# control_v2.net
KiCad netlist of a schematic drawn in EAGLE
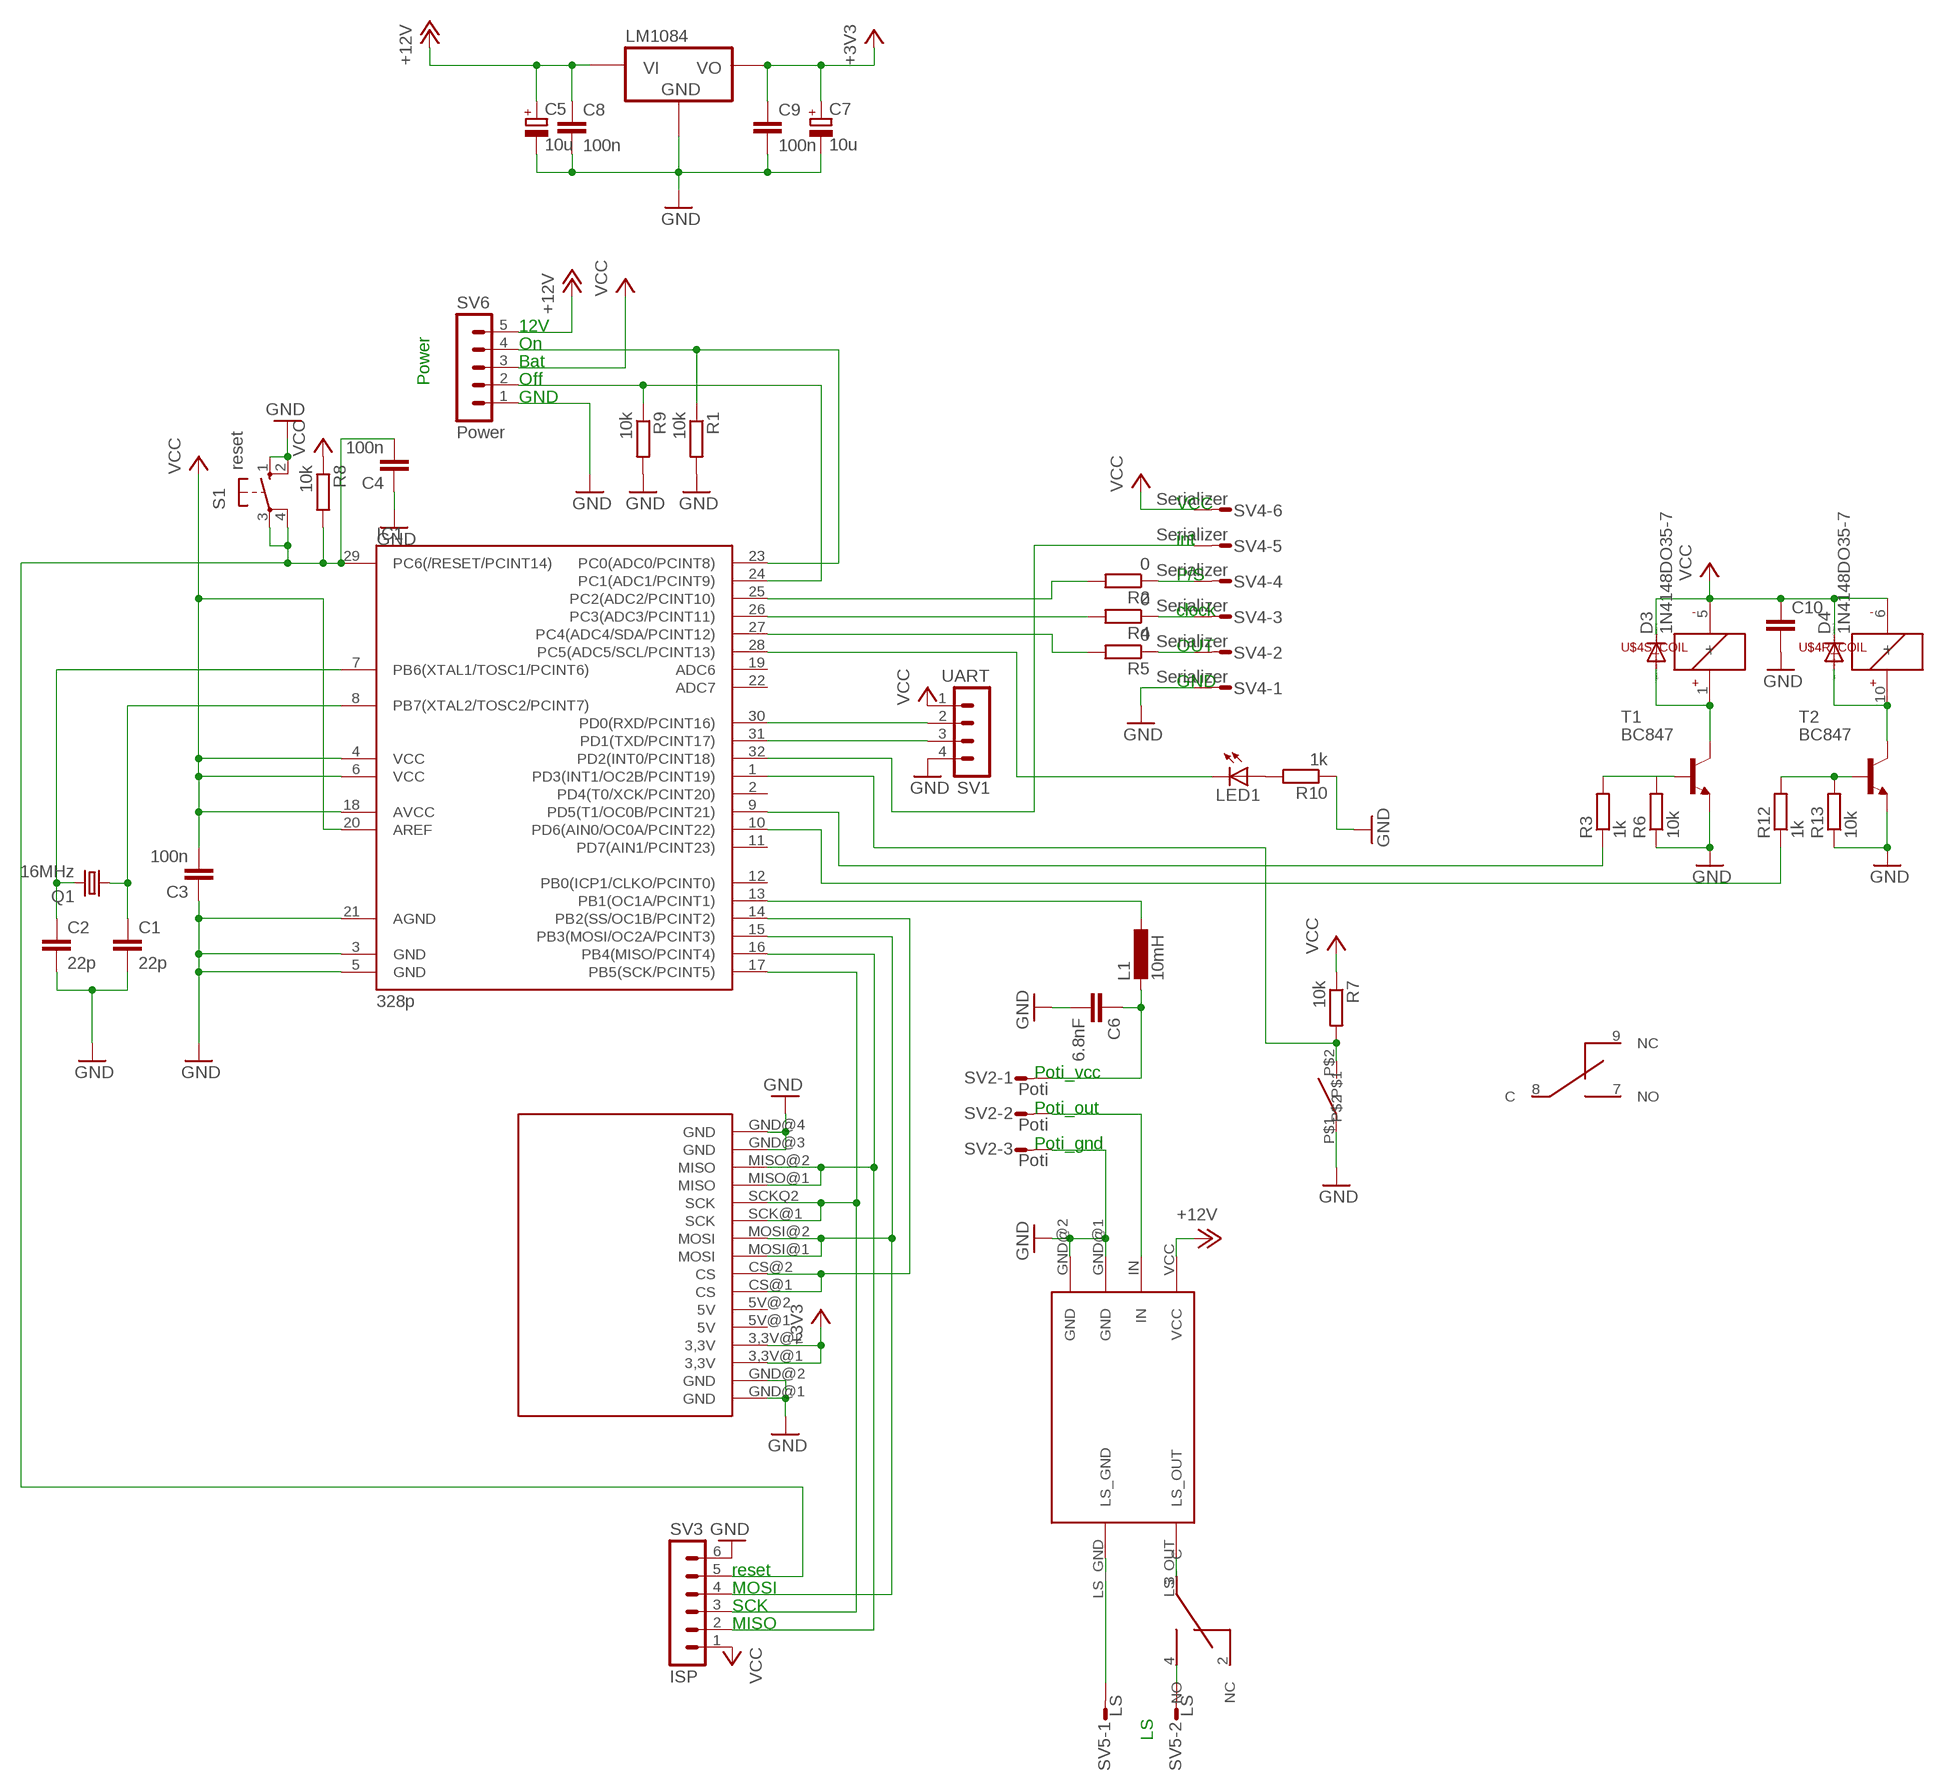
[diagram p0: schematic, sheet 1]

(export (version "E")
  (design (tool "Eeschema 10.0.6"))
  (components
    (comp (ref "C1")
      (value "22p")
      (footprint "eagle-import:C1206")
      (libsource (lib "eagle-import") (part "C-EUC1206"))
    )
    (comp (ref "C2")
      (value "22p")
      (footprint "eagle-import:C1206")
      (libsource (lib "eagle-import") (part "C-EUC1206"))
    )
    (comp (ref "C3")
      (value "100n")
      (footprint "eagle-import:C1206")
      (libsource (lib "eagle-import") (part "C-EUC1206"))
    )
    (comp (ref "C4")
      (value "100n")
      (footprint "eagle-import:C1206")
      (libsource (lib "eagle-import") (part "C-EUC1206"))
    )
    (comp (ref "C5")
      (value "10u")
      (footprint "eagle-import:E2,5-7")
      (libsource (lib "eagle-import") (part "CPOL-EUE2.5-7"))
    )
    (comp (ref "C6")
      (value "6.8nF")
      (footprint "eagle-import:C050-024X044")
      (libsource (lib "eagle-import") (part "C-EU050-024X044"))
    )
    (comp (ref "C7")
      (value "10u")
      (footprint "eagle-import:E2,5-7")
      (libsource (lib "eagle-import") (part "CPOL-EUE2.5-7"))
    )
    (comp (ref "C8")
      (value "100n")
      (footprint "eagle-import:C1206")
      (libsource (lib "eagle-import") (part "C-EUC1206"))
    )
    (comp (ref "C9")
      (value "100n")
      (footprint "eagle-import:C1206")
      (libsource (lib "eagle-import") (part "C-EUC1206"))
    )
    (comp (ref "C10")
      (value "C-EUC1206")
      (footprint "eagle-import:C1206")
      (libsource (lib "eagle-import") (part "C-EUC1206"))
    )
    (comp (ref "D3")
      (value "1N4148DO35-7")
      (footprint "eagle-import:DO35-7")
      (libsource (lib "eagle-import") (part "1N4148DO35-7"))
    )
    (comp (ref "D4")
      (value "1N4148DO35-7")
      (footprint "eagle-import:DO35-7")
      (libsource (lib "eagle-import") (part "1N4148DO35-7"))
    )
    (comp (ref "IC1")
      (value "328p")
      (footprint "eagle-import:TQFP32-08")
      (libsource (lib "eagle-import") (part "MEGA48/88/168-AU"))
    )
    (comp (ref "L1")
      (value "10mH")
      (footprint "eagle-import:0207_5V")
      (libsource (lib "eagle-import") (part "L-EU0207/5V"))
    )
    (comp (ref "LED1")
      (value "LEDCHIPLED_1206")
      (footprint "eagle-import:CHIPLED_1206")
      (libsource (lib "eagle-import") (part "LEDCHIPLED_1206"))
    )
    (comp (ref "Q1")
      (value "16MHz")
      (footprint "eagle-import:HC49UP")
      (libsource (lib "eagle-import") (part "CRYSTALHC49UP"))
    )
    (comp (ref "R1")
      (value "10k")
      (footprint "eagle-import:M1206")
      (libsource (lib "eagle-import") (part "R-EU_M1206"))
    )
    (comp (ref "R2")
      (value "0")
      (footprint "eagle-import:M1206")
      (libsource (lib "eagle-import") (part "R-EU_M1206"))
    )
    (comp (ref "R3")
      (value "1k")
      (footprint "eagle-import:M1206")
      (libsource (lib "eagle-import") (part "R-EU_M1206"))
    )
    (comp (ref "R4")
      (value "0")
      (footprint "eagle-import:M1206")
      (libsource (lib "eagle-import") (part "R-EU_M1206"))
    )
    (comp (ref "R5")
      (value "0")
      (footprint "eagle-import:M1206")
      (libsource (lib "eagle-import") (part "R-EU_M1206"))
    )
    (comp (ref "R6")
      (value "10k")
      (footprint "eagle-import:M1206")
      (libsource (lib "eagle-import") (part "R-EU_M1206"))
    )
    (comp (ref "R7")
      (value "10k")
      (footprint "eagle-import:M1206")
      (libsource (lib "eagle-import") (part "R-EU_M1206"))
    )
    (comp (ref "R8")
      (value "10k")
      (footprint "eagle-import:M1206")
      (libsource (lib "eagle-import") (part "R-EU_M1206"))
    )
    (comp (ref "R9")
      (value "10k")
      (footprint "eagle-import:M1206")
      (libsource (lib "eagle-import") (part "R-EU_M1206"))
    )
    (comp (ref "R10")
      (value "1k")
      (footprint "eagle-import:M1206")
      (libsource (lib "eagle-import") (part "R-EU_M1206"))
    )
    (comp (ref "R12")
      (value "1k")
      (footprint "eagle-import:M1206")
      (libsource (lib "eagle-import") (part "R-EU_M1206"))
    )
    (comp (ref "R13")
      (value "10k")
      (footprint "eagle-import:M1206")
      (libsource (lib "eagle-import") (part "R-EU_M1206"))
    )
    (comp (ref "S1")
      (value "reset")
      (footprint "eagle-import:B3F-10XX")
      (fields (field (name "MPN") "B3F-1000"))
      (libsource (lib "eagle-import") (part "10-XX"))
    )
    (comp (ref "SV1")
      (value "UART")
      (footprint "eagle-import:MA04-1")
      (libsource (lib "eagle-import") (part "MA04-1"))
    )
    (comp (ref "SV2")
      (value "Poti")
      (footprint "eagle-import:S03P")
      (libsource (lib "eagle-import") (part "S03P"))
    )
    (comp (ref "SV3")
      (value "ISP")
      (footprint "eagle-import:MA06-1")
      (libsource (lib "eagle-import") (part "MA06-1"))
    )
    (comp (ref "SV4")
      (value "Serializer")
      (footprint "eagle-import:S06P")
      (libsource (lib "eagle-import") (part "S06P"))
    )
    (comp (ref "SV5")
      (value "LS")
      (footprint "eagle-import:S02P")
      (libsource (lib "eagle-import") (part "S02P"))
    )
    (comp (ref "SV6")
      (value "Power")
      (footprint "eagle-import:MA05-1")
      (libsource (lib "eagle-import") (part "MA05-1"))
    )
    (comp (ref "T1")
      (value "BC847")
      (footprint "eagle-import:SOT23-BEC")
      (libsource (lib "eagle-import") (part "-NPN-SOT23-BECBC847"))
    )
    (comp (ref "T2")
      (value "BC847")
      (footprint "eagle-import:SOT23-BEC")
      (libsource (lib "eagle-import") (part "-NPN-SOT23-BECBC847"))
    )
    (comp (ref "U$1")
      (value "TILT")
      (footprint "eagle-import:TILT")
      (libsource (lib "eagle-import") (part "TILT"))
    )
    (comp (ref "U$2")
      (value "AMP")
      (footprint "eagle-import:AMP")
      (libsource (lib "eagle-import") (part "AMP"))
    )
    (comp (ref "U$3")
      (value "SD_CARD_HOLDER")
      (footprint "eagle-import:SD_CARD_HOLDER")
      (libsource (lib "eagle-import") (part "SD_CARD_HOLDER"))
    )
    (comp (ref "U$4")
      (value "EB2-4.5TNU")
      (footprint "eagle-import:10PIN_SMD_RELAY")
      (libsource (lib "eagle-import") (part "EB2-4.5TNU"))
    )
    (comp (ref "U$5")
      (value "LD1117")
      (footprint "eagle-import:TO220V")
      (libsource (lib "eagle-import") (part "LD1117"))
    )
  )
  (nets
    (net (code "1") (name "+3V3") (class "Default")
      (node (ref "C7") (pin "+") (pinfunction "+_+") (pintype "passive"))
      (node (ref "C9") (pin "1") (pinfunction "1_1") (pintype "passive"))
      (node (ref "U$3") (pin "3,3V@1") (pinfunction "3,3V_3,3V@1") (pintype "bidirectional"))
      (node (ref "U$3") (pin "3,3V@2") (pinfunction "3,3V_3,3V@2") (pintype "bidirectional"))
      (node (ref "U$5") (pin "2") (pinfunction "VO_2") (pintype "bidirectional"))
    )
    (net (code "2") (name "+12V") (class "Default")
      (node (ref "C5") (pin "+") (pinfunction "+_+") (pintype "passive"))
      (node (ref "C8") (pin "1") (pinfunction "1_1") (pintype "passive"))
      (node (ref "SV6") (pin "5") (pinfunction "5_5") (pintype "passive"))
      (node (ref "U$2") (pin "VCC") (pinfunction "VCC_VCC") (pintype "bidirectional"))
      (node (ref "U$5") (pin "3") (pinfunction "VI_3") (pintype "input"))
    )
    (net (code "3") (name "GND") (class "Default")
      (node (ref "C1") (pin "2") (pinfunction "2_2") (pintype "passive"))
      (node (ref "C10") (pin "2") (pinfunction "2_2") (pintype "passive"))
      (node (ref "C2") (pin "2") (pinfunction "2_2") (pintype "passive"))
      (node (ref "C3") (pin "1") (pinfunction "1_1") (pintype "passive"))
      (node (ref "C4") (pin "1") (pinfunction "1_1") (pintype "passive"))
      (node (ref "C5") (pin "-") (pinfunction "-_-") (pintype "passive"))
      (node (ref "C6") (pin "2") (pinfunction "2_2") (pintype "passive"))
      (node (ref "C7") (pin "-") (pinfunction "-_-") (pintype "passive"))
      (node (ref "C8") (pin "2") (pinfunction "2_2") (pintype "passive"))
      (node (ref "C9") (pin "2") (pinfunction "2_2") (pintype "passive"))
      (node (ref "IC1") (pin "21") (pinfunction "AGND_21") (pintype "power_in"))
      (node (ref "IC1") (pin "3") (pinfunction "GND_3") (pintype "power_in"))
      (node (ref "IC1") (pin "5") (pinfunction "GND_5") (pintype "power_in"))
      (node (ref "R1") (pin "2") (pinfunction "2_2") (pintype "passive"))
      (node (ref "R10") (pin "1") (pinfunction "1_1") (pintype "passive"))
      (node (ref "R13") (pin "1") (pinfunction "1_1") (pintype "passive"))
      (node (ref "R6") (pin "1") (pinfunction "1_1") (pintype "passive"))
      (node (ref "R9") (pin "2") (pinfunction "2_2") (pintype "passive"))
      (node (ref "S1") (pin "1") (pinfunction "S_1") (pintype "passive"))
      (node (ref "S1") (pin "2") (pinfunction "S1_2") (pintype "passive"))
      (node (ref "SV1") (pin "4") (pinfunction "4_4") (pintype "passive"))
      (node (ref "SV2") (pin "3") (pinfunction "S_3") (pintype "passive"))
      (node (ref "SV3") (pin "6") (pinfunction "6_6") (pintype "passive"))
      (node (ref "SV4") (pin "1") (pinfunction "S_1") (pintype "passive"))
      (node (ref "SV6") (pin "1") (pinfunction "1_1") (pintype "passive"))
      (node (ref "T1") (pin "E") (pinfunction "E_E") (pintype "passive"))
      (node (ref "T2") (pin "E") (pinfunction "E_E") (pintype "passive"))
      (node (ref "U$1") (pin "P$1") (pinfunction "P$1_P$1") (pintype "bidirectional"))
      (node (ref "U$2") (pin "GND@1") (pinfunction "GND_GND@1") (pintype "bidirectional"))
      (node (ref "U$2") (pin "GND@2") (pinfunction "GND_GND@2") (pintype "bidirectional"))
      (node (ref "U$3") (pin "GND@1") (pinfunction "GND_GND@1") (pintype "bidirectional"))
      (node (ref "U$3") (pin "GND@2") (pinfunction "GND_GND@2") (pintype "bidirectional"))
      (node (ref "U$3") (pin "GND@3") (pinfunction "GND_GND@3") (pintype "bidirectional"))
      (node (ref "U$3") (pin "GND@4") (pinfunction "GND_GND@4") (pintype "bidirectional"))
      (node (ref "U$5") (pin "1") (pinfunction "GND_1") (pintype "bidirectional"))
    )
    (net (code "4") (name "Net-(IC1-PB1(OC1A{slash}PCINT1))") (class "Default")
      (node (ref "IC1") (pin "13") (pinfunction "PB1(OC1A/PCINT1)_13") (pintype "bidirectional"))
      (node (ref "L1") (pin "1") (pinfunction "1_1") (pintype "passive"))
    )
    (net (code "5") (name "Net-(IC1-PB2(SS{slash}OC1B{slash}PCINT2))") (class "Default")
      (node (ref "IC1") (pin "14") (pinfunction "PB2(SS/OC1B/PCINT2)_14") (pintype "bidirectional"))
      (node (ref "U$3") (pin "CS@1") (pinfunction "CS_CS@1") (pintype "bidirectional"))
      (node (ref "U$3") (pin "CS@2") (pinfunction "CS_CS@2") (pintype "bidirectional"))
    )
    (net (code "6") (name "Net-(IC1-PB3(MOSI{slash}OC2A{slash}PCINT3))") (class "Default")
      (node (ref "IC1") (pin "15") (pinfunction "PB3(MOSI/OC2A/PCINT3)_15") (pintype "bidirectional"))
      (node (ref "SV3") (pin "4") (pinfunction "4_4") (pintype "passive"))
      (node (ref "U$3") (pin "MOSI@1") (pinfunction "MOSI_MOSI@1") (pintype "bidirectional"))
      (node (ref "U$3") (pin "MOSI@2") (pinfunction "MOSI_MOSI@2") (pintype "bidirectional"))
    )
    (net (code "7") (name "Net-(IC1-PB4(MISO{slash}PCINT4))") (class "Default")
      (node (ref "IC1") (pin "16") (pinfunction "PB4(MISO/PCINT4)_16") (pintype "bidirectional"))
      (node (ref "SV3") (pin "2") (pinfunction "2_2") (pintype "passive"))
      (node (ref "U$3") (pin "MISO@1") (pinfunction "MISO_MISO@1") (pintype "bidirectional"))
      (node (ref "U$3") (pin "MISO@2") (pinfunction "MISO_MISO@2") (pintype "bidirectional"))
    )
    (net (code "8") (name "Net-(IC1-PB5(SCK{slash}PCINT5))") (class "Default")
      (node (ref "IC1") (pin "17") (pinfunction "PB5(SCK/PCINT5)_17") (pintype "bidirectional"))
      (node (ref "SV3") (pin "3") (pinfunction "3_3") (pintype "passive"))
      (node (ref "U$3") (pin "SCK@1") (pinfunction "SCK_SCK@1") (pintype "bidirectional"))
      (node (ref "U$3") (pin "SCKQ2") (pinfunction "SCK_SCKQ2") (pintype "bidirectional"))
    )
    (net (code "9") (name "Net-(IC1-PB6(XTAL1{slash}TOSC1{slash}PCINT6))") (class "Default")
      (node (ref "C2") (pin "1") (pinfunction "1_1") (pintype "passive"))
      (node (ref "IC1") (pin "7") (pinfunction "PB6(XTAL1/TOSC1/PCINT6)_7") (pintype "bidirectional"))
      (node (ref "Q1") (pin "2") (pinfunction "2_2") (pintype "passive"))
    )
    (net (code "10") (name "Net-(IC1-PB7(XTAL2{slash}TOSC2{slash}PCINT7))") (class "Default")
      (node (ref "C1") (pin "1") (pinfunction "1_1") (pintype "passive"))
      (node (ref "IC1") (pin "8") (pinfunction "PB7(XTAL2/TOSC2/PCINT7)_8") (pintype "bidirectional"))
      (node (ref "Q1") (pin "1") (pinfunction "1_1") (pintype "passive"))
    )
    (net (code "11") (name "Net-(IC1-PC0(ADC0{slash}PCINT8))") (class "Default")
      (node (ref "IC1") (pin "23") (pinfunction "PC0(ADC0/PCINT8)_23") (pintype "bidirectional"))
      (node (ref "R1") (pin "1") (pinfunction "1_1") (pintype "passive"))
      (node (ref "SV6") (pin "4") (pinfunction "4_4") (pintype "passive"))
    )
    (net (code "12") (name "Net-(IC1-PC1(ADC1{slash}PCINT9))") (class "Default")
      (node (ref "IC1") (pin "24") (pinfunction "PC1(ADC1/PCINT9)_24") (pintype "bidirectional"))
      (node (ref "R9") (pin "1") (pinfunction "1_1") (pintype "passive"))
      (node (ref "SV6") (pin "2") (pinfunction "2_2") (pintype "passive"))
    )
    (net (code "13") (name "Net-(IC1-PC2(ADC2{slash}PCINT10))") (class "Default")
      (node (ref "IC1") (pin "25") (pinfunction "PC2(ADC2/PCINT10)_25") (pintype "bidirectional"))
      (node (ref "R2") (pin "2") (pinfunction "2_2") (pintype "passive"))
    )
    (net (code "14") (name "Net-(IC1-PC3(ADC3{slash}PCINT11))") (class "Default")
      (node (ref "IC1") (pin "26") (pinfunction "PC3(ADC3/PCINT11)_26") (pintype "bidirectional"))
      (node (ref "R4") (pin "2") (pinfunction "2_2") (pintype "passive"))
    )
    (net (code "15") (name "Net-(IC1-PC4(ADC4{slash}SDA{slash}PCINT12))") (class "Default")
      (node (ref "IC1") (pin "27") (pinfunction "PC4(ADC4/SDA/PCINT12)_27") (pintype "bidirectional"))
      (node (ref "R5") (pin "2") (pinfunction "2_2") (pintype "passive"))
    )
    (net (code "16") (name "Net-(IC1-PC5(ADC5{slash}SCL{slash}PCINT13))") (class "Default")
      (node (ref "IC1") (pin "28") (pinfunction "PC5(ADC5/SCL/PCINT13)_28") (pintype "bidirectional"))
      (node (ref "LED1") (pin "C") (pinfunction "C_C") (pintype "passive"))
    )
    (net (code "17") (name "Net-(IC1-PC6({slash}RESET{slash}PCINT14))") (class "Default")
      (node (ref "C4") (pin "2") (pinfunction "2_2") (pintype "passive"))
      (node (ref "IC1") (pin "29") (pinfunction "PC6(/RESET/PCINT14)_29") (pintype "bidirectional"))
      (node (ref "R8") (pin "2") (pinfunction "2_2") (pintype "passive"))
      (node (ref "S1") (pin "3") (pinfunction "P_3") (pintype "passive"))
      (node (ref "S1") (pin "4") (pinfunction "P1_4") (pintype "passive"))
      (node (ref "SV3") (pin "5") (pinfunction "5_5") (pintype "passive"))
    )
    (net (code "18") (name "Net-(IC1-PD0(RXD{slash}PCINT16))") (class "Default")
      (node (ref "IC1") (pin "30") (pinfunction "PD0(RXD/PCINT16)_30") (pintype "bidirectional"))
      (node (ref "SV1") (pin "2") (pinfunction "2_2") (pintype "passive"))
    )
    (net (code "19") (name "Net-(IC1-PD1(TXD{slash}PCINT17))") (class "Default")
      (node (ref "IC1") (pin "31") (pinfunction "PD1(TXD/PCINT17)_31") (pintype "bidirectional"))
      (node (ref "SV1") (pin "3") (pinfunction "3_3") (pintype "passive"))
    )
    (net (code "20") (name "Net-(IC1-PD2(INT0{slash}PCINT18))") (class "Default")
      (node (ref "IC1") (pin "32") (pinfunction "PD2(INT0/PCINT18)_32") (pintype "bidirectional"))
      (node (ref "SV4") (pin "5") (pinfunction "S_5") (pintype "passive"))
    )
    (net (code "21") (name "Net-(IC1-PD3(INT1{slash}OC2B{slash}PCINT19))") (class "Default")
      (node (ref "IC1") (pin "1") (pinfunction "PD3(INT1/OC2B/PCINT19)_1") (pintype "bidirectional"))
      (node (ref "R7") (pin "2") (pinfunction "2_2") (pintype "passive"))
      (node (ref "U$1") (pin "P$2") (pinfunction "P$2_P$2") (pintype "bidirectional"))
    )
    (net (code "22") (name "Net-(IC1-PD5(T1{slash}OC0B{slash}PCINT21))") (class "Default")
      (node (ref "IC1") (pin "9") (pinfunction "PD5(T1/OC0B/PCINT21)_9") (pintype "bidirectional"))
      (node (ref "R3") (pin "1") (pinfunction "1_1") (pintype "passive"))
    )
    (net (code "23") (name "Net-(IC1-PD6(AIN0{slash}OC0A{slash}PCINT22))") (class "Default")
      (node (ref "IC1") (pin "10") (pinfunction "PD6(AIN0/OC0A/PCINT22)_10") (pintype "bidirectional"))
      (node (ref "R12") (pin "1") (pinfunction "1_1") (pintype "passive"))
    )
    (net (code "24") (name "Net-(LED1-PadA)") (class "Default")
      (node (ref "LED1") (pin "A") (pinfunction "A_A") (pintype "passive"))
      (node (ref "R10") (pin "2") (pinfunction "2_2") (pintype "passive"))
    )
    (net (code "25") (name "Net-(R3-Pad2)") (class "Default")
      (node (ref "R3") (pin "2") (pinfunction "2_2") (pintype "passive"))
      (node (ref "R6") (pin "2") (pinfunction "2_2") (pintype "passive"))
      (node (ref "T1") (pin "B") (pinfunction "B_B") (pintype "passive"))
    )
    (net (code "26") (name "Net-(R12-Pad2)") (class "Default")
      (node (ref "R12") (pin "2") (pinfunction "2_2") (pintype "passive"))
      (node (ref "R13") (pin "2") (pinfunction "2_2") (pintype "passive"))
      (node (ref "T2") (pin "B") (pinfunction "B_B") (pintype "passive"))
    )
    (net (code "27") (name "Net-(SV2A-S)") (class "Default")
      (node (ref "C6") (pin "1") (pinfunction "1_1") (pintype "passive"))
      (node (ref "L1") (pin "2") (pinfunction "2_2") (pintype "passive"))
      (node (ref "SV2") (pin "1") (pinfunction "S_1") (pintype "passive"))
    )
    (net (code "28") (name "Net-(SV2B-S)") (class "Default")
      (node (ref "SV2") (pin "2") (pinfunction "S_2") (pintype "passive"))
      (node (ref "U$2") (pin "IN") (pinfunction "IN_IN") (pintype "bidirectional"))
    )
    (net (code "29") (name "Net-(SV4B-S)") (class "Default")
      (node (ref "R5") (pin "1") (pinfunction "1_1") (pintype "passive"))
      (node (ref "SV4") (pin "2") (pinfunction "S_2") (pintype "passive"))
    )
    (net (code "30") (name "Net-(SV4C-S)") (class "Default")
      (node (ref "R4") (pin "1") (pinfunction "1_1") (pintype "passive"))
      (node (ref "SV4") (pin "3") (pinfunction "S_3") (pintype "passive"))
    )
    (net (code "31") (name "Net-(SV4D-S)") (class "Default")
      (node (ref "R2") (pin "1") (pinfunction "1_1") (pintype "passive"))
      (node (ref "SV4") (pin "4") (pinfunction "S_4") (pintype "passive"))
    )
    (net (code "32") (name "Net-(SV5A-S)") (class "Default")
      (node (ref "SV5") (pin "1") (pinfunction "S_1") (pintype "passive"))
      (node (ref "U$2") (pin "LS_GND") (pinfunction "LS_GND_LS_GND") (pintype "bidirectional"))
    )
    (net (code "33") (name "Net-(SV5B-S)") (class "Default")
      (node (ref "SV5") (pin "2") (pinfunction "S_2") (pintype "passive"))
      (node (ref "U$4") (pin "4") (pinfunction "NO_4") (pintype "bidirectional"))
    )
    (net (code "34") (name "Net-(U$4A-+)") (class "Default")
      (node (ref "D4") (pin "A") (pinfunction "A_A") (pintype "passive"))
      (node (ref "T2") (pin "C") (pinfunction "C_C") (pintype "passive"))
      (node (ref "U$4") (pin "10") (pinfunction "+_10") (pintype "bidirectional"))
    )
    (net (code "35") (name "Net-(U$4C-C)") (class "Default")
      (node (ref "U$2") (pin "LS_OUT") (pinfunction "LS_OUT_LS_OUT") (pintype "bidirectional"))
      (node (ref "U$4") (pin "3") (pinfunction "C_3") (pintype "bidirectional"))
    )
    (net (code "36") (name "Net-(U$4D-+)") (class "Default")
      (node (ref "D3") (pin "A") (pinfunction "A_A") (pintype "passive"))
      (node (ref "T1") (pin "C") (pinfunction "C_C") (pintype "passive"))
      (node (ref "U$4") (pin "1") (pinfunction "+_1") (pintype "bidirectional"))
    )
    (net (code "37") (name "VCC") (class "Default")
      (node (ref "C10") (pin "1") (pinfunction "1_1") (pintype "passive"))
      (node (ref "C3") (pin "2") (pinfunction "2_2") (pintype "passive"))
      (node (ref "D3") (pin "C") (pinfunction "C_C") (pintype "passive"))
      (node (ref "D4") (pin "C") (pinfunction "C_C") (pintype "passive"))
      (node (ref "IC1") (pin "18") (pinfunction "AVCC_18") (pintype "passive"))
      (node (ref "IC1") (pin "20") (pinfunction "AREF_20") (pintype "passive"))
      (node (ref "IC1") (pin "4") (pinfunction "VCC_4") (pintype "power_in"))
      (node (ref "IC1") (pin "6") (pinfunction "VCC_6") (pintype "power_in"))
      (node (ref "R7") (pin "1") (pinfunction "1_1") (pintype "passive"))
      (node (ref "R8") (pin "1") (pinfunction "1_1") (pintype "passive"))
      (node (ref "SV1") (pin "1") (pinfunction "1_1") (pintype "passive"))
      (node (ref "SV3") (pin "1") (pinfunction "1_1") (pintype "passive"))
      (node (ref "SV4") (pin "6") (pinfunction "S_6") (pintype "passive"))
      (node (ref "SV6") (pin "3") (pinfunction "3_3") (pintype "passive"))
      (node (ref "U$4") (pin "5") (pinfunction "-_5") (pintype "bidirectional"))
      (node (ref "U$4") (pin "6") (pinfunction "-_6") (pintype "bidirectional"))
    )
    (net (code "38") (name "unconnected-(IC1-ADC6-Pad19)") (class "Default")
      (node (ref "IC1") (pin "19") (pinfunction "ADC6_19") (pintype "passive"))
    )
    (net (code "39") (name "unconnected-(IC1-ADC7-Pad22)") (class "Default")
      (node (ref "IC1") (pin "22") (pinfunction "ADC7_22") (pintype "passive"))
    )
    (net (code "40") (name "unconnected-(IC1-PB0(ICP1{slash}CLKO{slash}PCINT0)-Pad12)") (class "Default")
      (node (ref "IC1") (pin "12") (pinfunction "PB0(ICP1/CLKO/PCINT0)_12") (pintype "bidirectional"))
    )
    (net (code "41") (name "unconnected-(IC1-PD4(T0{slash}XCK{slash}PCINT20)-Pad2)") (class "Default")
      (node (ref "IC1") (pin "2") (pinfunction "PD4(T0/XCK/PCINT20)_2") (pintype "bidirectional"))
    )
    (net (code "42") (name "unconnected-(IC1-PD7(AIN1{slash}PCINT23)-Pad11)") (class "Default")
      (node (ref "IC1") (pin "11") (pinfunction "PD7(AIN1/PCINT23)_11") (pintype "bidirectional"))
    )
    (net (code "43") (name "unconnected-(U$3-5V-Pad5V@1)") (class "Default")
      (node (ref "U$3") (pin "5V@1") (pinfunction "5V_5V@1") (pintype "bidirectional"))
    )
    (net (code "44") (name "unconnected-(U$3-5V-Pad5V@2)") (class "Default")
      (node (ref "U$3") (pin "5V@2") (pinfunction "5V_5V@2") (pintype "bidirectional"))
    )
    (net (code "45") (name "unconnected-(U$4B-C-Pad8)") (class "Default")
      (node (ref "U$4") (pin "8") (pinfunction "C_8") (pintype "bidirectional"))
    )
    (net (code "46") (name "unconnected-(U$4B-NC-Pad9)") (class "Default")
      (node (ref "U$4") (pin "9") (pinfunction "NC_9") (pintype "bidirectional"))
    )
    (net (code "47") (name "unconnected-(U$4B-NO-Pad7)") (class "Default")
      (node (ref "U$4") (pin "7") (pinfunction "NO_7") (pintype "bidirectional"))
    )
    (net (code "48") (name "unconnected-(U$4C-NC-Pad2)") (class "Default")
      (node (ref "U$4") (pin "2") (pinfunction "NC_2") (pintype "bidirectional"))
    )
  )
)
